# Shield_Play.net
KiCad netlist of a schematic drawn in EAGLE
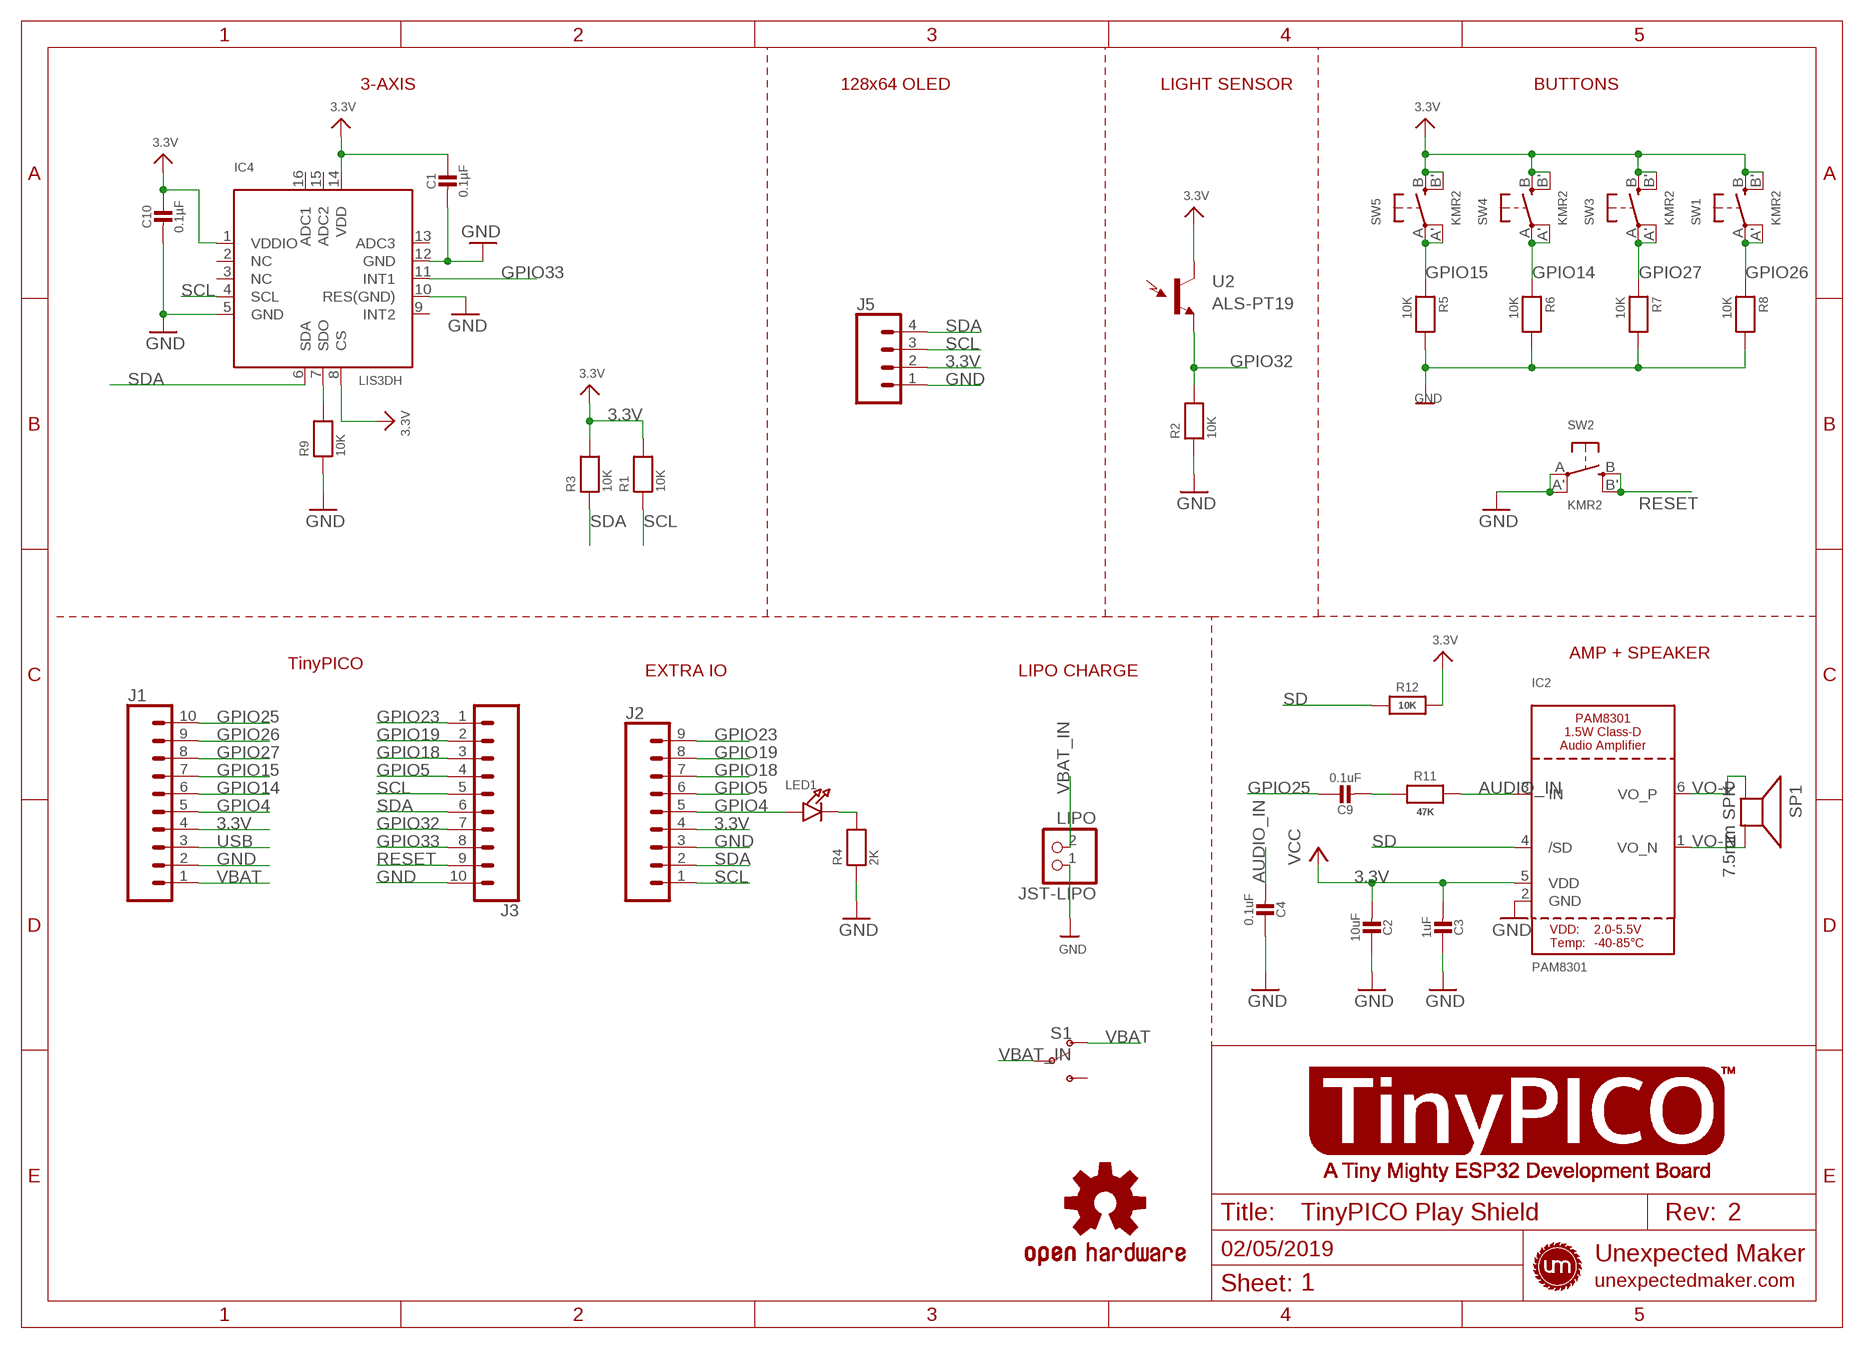
[diagram p0: schematic, sheet 1]

(export (version "E")
  (design (tool "Eeschema 10.0.6"))
  (components
    (comp (ref "C1")
      (value "0.1µF")
      (footprint "eagle-import:_0603MP")
      (libsource (lib "eagle-import") (part "CAP_CERAMIC_0603MP"))
    )
    (comp (ref "C2")
      (value "10uF")
      (footprint "eagle-import:_0603MP")
      (libsource (lib "eagle-import") (part "CAP_CERAMIC_0603MP"))
    )
    (comp (ref "C3")
      (value "1uF")
      (footprint "eagle-import:_0603MP")
      (libsource (lib "eagle-import") (part "CAP_CERAMIC_0603MP"))
    )
    (comp (ref "C4")
      (value "0.1uF")
      (footprint "eagle-import:_0603MP")
      (libsource (lib "eagle-import") (part "CAP_CERAMIC_0603MP"))
    )
    (comp (ref "C9")
      (value "0.1uF")
      (footprint "eagle-import:_0603MP")
      (libsource (lib "eagle-import") (part "CAP_CERAMIC_0603MP"))
    )
    (comp (ref "C10")
      (value "0.1µF")
      (footprint "eagle-import:_0603MP")
      (libsource (lib "eagle-import") (part "CAP_CERAMIC_0603MP"))
    )
    (comp (ref "IC2")
      (value "PAM8301")
      (footprint "eagle-import:SOT23-6")
      (libsource (lib "eagle-import") (part "PAM8301"))
    )
    (comp (ref "IC4")
      (value "LIS3DH")
      (footprint "eagle-import:LGA16_3X3MM")
      (libsource (lib "eagle-import") (part "ACCEL_LIS3DHTR"))
    )
    (comp (ref "J1")
      (value "TINYPICO_HEADER_10NO_SILK_PTH_FEMALE")
      (footprint "eagle-import:1X10_NO_SILK")
      (libsource (lib "eagle-import") (part "TINYPICO_HEADER_10NO_SILK_PTH_FEMALE"))
    )
    (comp (ref "J2")
      (value "CONN_09NO_SILK")
      (footprint "eagle-import:1X09_NO_SILK")
      (libsource (lib "eagle-import") (part "CONN_09NO_SILK"))
    )
    (comp (ref "J3")
      (value "TINYPICO_HEADER_10NO_SILK_PTH_FEMALE")
      (footprint "eagle-import:1X10_NO_SILK")
      (libsource (lib "eagle-import") (part "TINYPICO_HEADER_10NO_SILK_PTH_FEMALE"))
    )
    (comp (ref "J5")
      (value "CONN_041X04_NO_SILK")
      (footprint "eagle-import:1X04_NO_SILK")
      (libsource (lib "eagle-import") (part "CONN_041X04_NO_SILK"))
    )
    (comp (ref "JST-LIPO")
      (value "LIPO")
      (footprint "eagle-import:JSTPH2")
      (libsource (lib "eagle-import") (part "JST_2PIN"))
    )
    (comp (ref "LED1")
      (value "LED0603_NOOUTLINE")
      (footprint "eagle-import:CHIPLED_0603_NOOUTLINE")
      (libsource (lib "eagle-import") (part "LED0603_NOOUTLINE"))
    )
    (comp (ref "LOGO1")
      (value "OSHW-LOGOS")
      (footprint "eagle-import:OSHW-LOGO-S")
      (libsource (lib "eagle-import") (part "OSHW-LOGOS"))
    )
    (comp (ref "R1")
      (value "10K")
      (footprint "eagle-import:_0603MP")
      (libsource (lib "eagle-import") (part "RESISTOR_0603MP"))
    )
    (comp (ref "R2")
      (value "10K")
      (footprint "eagle-import:_0603MP")
      (libsource (lib "eagle-import") (part "RESISTOR_0603MP"))
    )
    (comp (ref "R3")
      (value "10K")
      (footprint "eagle-import:_0603MP")
      (libsource (lib "eagle-import") (part "RESISTOR_0603MP"))
    )
    (comp (ref "R4")
      (value "2K")
      (footprint "eagle-import:_0603MP")
      (libsource (lib "eagle-import") (part "RESISTOR_0603MP"))
    )
    (comp (ref "R5")
      (value "10K")
      (footprint "eagle-import:_0603MP")
      (libsource (lib "eagle-import") (part "RESISTOR_0603MP"))
    )
    (comp (ref "R6")
      (value "10K")
      (footprint "eagle-import:_0603MP")
      (libsource (lib "eagle-import") (part "RESISTOR_0603MP"))
    )
    (comp (ref "R7")
      (value "10K")
      (footprint "eagle-import:_0603MP")
      (libsource (lib "eagle-import") (part "RESISTOR_0603MP"))
    )
    (comp (ref "R8")
      (value "10K")
      (footprint "eagle-import:_0603MP")
      (libsource (lib "eagle-import") (part "RESISTOR_0603MP"))
    )
    (comp (ref "R9")
      (value "10K")
      (footprint "eagle-import:_0603MP")
      (libsource (lib "eagle-import") (part "RESISTOR_0603MP"))
    )
    (comp (ref "R11")
      (value "47K")
      (footprint "eagle-import:_0603MP")
      (libsource (lib "eagle-import") (part "RESISTOR_0603MP"))
    )
    (comp (ref "R12")
      (value "10K")
      (footprint "eagle-import:_0603MP")
      (libsource (lib "eagle-import") (part "RESISTOR_0603MP"))
    )
    (comp (ref "S1")
      (value "SPARKFUN-SWITCHES_SWITCH-SPDT-SMD-RIGHT-ANGLE")
      (footprint "eagle-import:SPARKFUN-SWITCHES_SWITCH_SPST_SMD_A")
      (libsource (lib "eagle-import") (part "SPARKFUN-SWITCHES_SWITCH-SPDT-SMD-RIGHT-ANGLE"))
    )
    (comp (ref "SP1")
      (value "7.5mm SPK")
      (footprint "eagle-import:BUZZER_SMT_7.5MM")
      (libsource (lib "eagle-import") (part "SPEAKER_7.5MM"))
    )
    (comp (ref "SW1")
      (value "KMR2")
      (footprint "eagle-import:BTN_KMR2_4.6X2.8")
      (libsource (lib "eagle-import") (part "SWITCH_TACT_SMT4.6X2.8"))
    )
    (comp (ref "SW2")
      (value "KMR2")
      (footprint "eagle-import:BTN_KMR2_4.6X2.8")
      (libsource (lib "eagle-import") (part "SWITCH_TACT_SMT4.6X2.8"))
    )
    (comp (ref "SW3")
      (value "KMR2")
      (footprint "eagle-import:BTN_KMR2_4.6X2.8")
      (libsource (lib "eagle-import") (part "SWITCH_TACT_SMT4.6X2.8"))
    )
    (comp (ref "SW4")
      (value "KMR2")
      (footprint "eagle-import:BTN_KMR2_4.6X2.8")
      (libsource (lib "eagle-import") (part "SWITCH_TACT_SMT4.6X2.8"))
    )
    (comp (ref "SW5")
      (value "KMR2")
      (footprint "eagle-import:BTN_KMR2_4.6X2.8")
      (libsource (lib "eagle-import") (part "SWITCH_TACT_SMT4.6X2.8"))
    )
    (comp (ref "U2")
      (value "ALS-PT19")
      (footprint "eagle-import:ALS-PT19")
      (libsource (lib "eagle-import") (part "LIGHT_SENSORALS"))
    )
  )
  (nets
    (net (code "1") (name "/AUDIO_IN") (class "Default")
      (node (ref "C4") (pin "2") (pinfunction "2_2") (pintype "passive"))
      (node (ref "IC2") (pin "3") (pinfunction "IN_3") (pintype "input"))
      (node (ref "R11") (pin "2") (pinfunction "2_2") (pintype "passive"))
    )
    (net (code "2") (name "/GPIO4") (class "Default")
      (node (ref "J1") (pin "5") (pinfunction "5_5") (pintype "passive"))
      (node (ref "J2") (pin "5") (pinfunction "5_5") (pintype "passive"))
      (node (ref "LED1") (pin "A") (pinfunction "A_A") (pintype "passive"))
    )
    (net (code "3") (name "/GPIO5") (class "Default")
      (node (ref "J2") (pin "6") (pinfunction "6_6") (pintype "passive"))
      (node (ref "J3") (pin "4") (pinfunction "4_4") (pintype "passive"))
    )
    (net (code "4") (name "/GPIO14") (class "Default")
      (node (ref "J1") (pin "6") (pinfunction "6_6") (pintype "passive"))
      (node (ref "R6") (pin "1") (pinfunction "1_1") (pintype "passive"))
      (node (ref "SW4") (pin "A") (pinfunction "P_A") (pintype "passive"))
      (node (ref "SW4") (pin "A'") (pinfunction "P1_A'") (pintype "passive"))
    )
    (net (code "5") (name "/GPIO15") (class "Default")
      (node (ref "J1") (pin "7") (pinfunction "7_7") (pintype "passive"))
      (node (ref "R5") (pin "1") (pinfunction "1_1") (pintype "passive"))
      (node (ref "SW5") (pin "A") (pinfunction "P_A") (pintype "passive"))
      (node (ref "SW5") (pin "A'") (pinfunction "P1_A'") (pintype "passive"))
    )
    (net (code "6") (name "/GPIO18") (class "Default")
      (node (ref "J2") (pin "7") (pinfunction "7_7") (pintype "passive"))
      (node (ref "J3") (pin "3") (pinfunction "3_3") (pintype "passive"))
    )
    (net (code "7") (name "/GPIO19") (class "Default")
      (node (ref "J2") (pin "8") (pinfunction "8_8") (pintype "passive"))
      (node (ref "J3") (pin "2") (pinfunction "2_2") (pintype "passive"))
    )
    (net (code "8") (name "/GPIO23") (class "Default")
      (node (ref "J2") (pin "9") (pinfunction "9_9") (pintype "passive"))
      (node (ref "J3") (pin "1") (pinfunction "1_1") (pintype "passive"))
    )
    (net (code "9") (name "/GPIO25") (class "Default")
      (node (ref "C9") (pin "1") (pinfunction "1_1") (pintype "passive"))
      (node (ref "J1") (pin "10") (pinfunction "10_10") (pintype "passive"))
    )
    (net (code "10") (name "/GPIO26") (class "Default")
      (node (ref "J1") (pin "9") (pinfunction "9_9") (pintype "passive"))
      (node (ref "R8") (pin "1") (pinfunction "1_1") (pintype "passive"))
      (node (ref "SW1") (pin "A") (pinfunction "P_A") (pintype "passive"))
      (node (ref "SW1") (pin "A'") (pinfunction "P1_A'") (pintype "passive"))
    )
    (net (code "11") (name "/GPIO27") (class "Default")
      (node (ref "J1") (pin "8") (pinfunction "8_8") (pintype "passive"))
      (node (ref "R7") (pin "1") (pinfunction "1_1") (pintype "passive"))
      (node (ref "SW3") (pin "A") (pinfunction "P_A") (pintype "passive"))
      (node (ref "SW3") (pin "A'") (pinfunction "P1_A'") (pintype "passive"))
    )
    (net (code "12") (name "/GPIO32") (class "Default")
      (node (ref "J3") (pin "7") (pinfunction "7_7") (pintype "passive"))
      (node (ref "R2") (pin "2") (pinfunction "2_2") (pintype "passive"))
      (node (ref "U2") (pin "E") (pinfunction "E1_E") (pintype "passive"))
    )
    (net (code "13") (name "/GPIO33") (class "Default")
      (node (ref "IC4") (pin "11") (pinfunction "INT1_11") (pintype "output"))
      (node (ref "J3") (pin "8") (pinfunction "8_8") (pintype "passive"))
    )
    (net (code "14") (name "/RESET") (class "Default")
      (node (ref "J3") (pin "9") (pinfunction "9_9") (pintype "passive"))
      (node (ref "SW2") (pin "B") (pinfunction "S_B") (pintype "passive"))
      (node (ref "SW2") (pin "B'") (pinfunction "S1_B'") (pintype "passive"))
    )
    (net (code "15") (name "/SCL") (class "Default")
      (node (ref "IC4") (pin "4") (pinfunction "SCL_4") (pintype "bidirectional"))
      (node (ref "J2") (pin "1") (pinfunction "1_1") (pintype "passive"))
      (node (ref "J3") (pin "5") (pinfunction "5_5") (pintype "passive"))
      (node (ref "J5") (pin "3") (pinfunction "3_3") (pintype "passive"))
      (node (ref "R1") (pin "1") (pinfunction "1_1") (pintype "passive"))
    )
    (net (code "16") (name "/SD") (class "Default")
      (node (ref "IC2") (pin "4") (pinfunction "/SD_4") (pintype "input"))
      (node (ref "R12") (pin "1") (pinfunction "1_1") (pintype "passive"))
    )
    (net (code "17") (name "/SDA") (class "Default")
      (node (ref "IC4") (pin "6") (pinfunction "SDA_6") (pintype "bidirectional"))
      (node (ref "J2") (pin "2") (pinfunction "2_2") (pintype "passive"))
      (node (ref "J3") (pin "6") (pinfunction "6_6") (pintype "passive"))
      (node (ref "J5") (pin "4") (pinfunction "4_4") (pintype "passive"))
      (node (ref "R3") (pin "1") (pinfunction "1_1") (pintype "passive"))
    )
    (net (code "18") (name "/USB") (class "Default")
      (node (ref "J1") (pin "3") (pinfunction "3_3") (pintype "passive"))
    )
    (net (code "19") (name "/VBAT") (class "Default")
      (node (ref "J1") (pin "1") (pinfunction "1_1") (pintype "passive"))
      (node (ref "S1") (pin "1") (pinfunction "O_1") (pintype "passive"))
    )
    (net (code "20") (name "/VBAT_IN") (class "Default")
      (node (ref "JST-LIPO") (pin "2") (pinfunction "2_2") (pintype "passive"))
      (node (ref "S1") (pin "2") (pinfunction "P_2") (pintype "passive"))
    )
    (net (code "21") (name "/VO-N") (class "Default")
      (node (ref "IC2") (pin "1") (pinfunction "VO_N_1") (pintype "output"))
      (node (ref "SP1") (pin "-") (pinfunction "-_-") (pintype "passive"))
    )
    (net (code "22") (name "/VO-P") (class "Default")
      (node (ref "IC2") (pin "6") (pinfunction "VO_P_6") (pintype "output"))
      (node (ref "SP1") (pin "+") (pinfunction "+_+") (pintype "passive"))
    )
    (net (code "23") (name "3.3V") (class "Default")
      (node (ref "C1") (pin "1") (pinfunction "1_1") (pintype "passive"))
      (node (ref "C10") (pin "1") (pinfunction "1_1") (pintype "passive"))
      (node (ref "C2") (pin "2") (pinfunction "2_2") (pintype "passive"))
      (node (ref "C3") (pin "2") (pinfunction "2_2") (pintype "passive"))
      (node (ref "IC2") (pin "5") (pinfunction "VDD_5") (pintype "power_in"))
      (node (ref "IC4") (pin "1") (pinfunction "VDDIO_1") (pintype "power_in"))
      (node (ref "IC4") (pin "14") (pinfunction "VDD_14") (pintype "power_in"))
      (node (ref "IC4") (pin "8") (pinfunction "CS_8") (pintype "input"))
      (node (ref "J1") (pin "4") (pinfunction "4_4") (pintype "passive"))
      (node (ref "J2") (pin "4") (pinfunction "4_4") (pintype "passive"))
      (node (ref "J5") (pin "2") (pinfunction "2_2") (pintype "passive"))
      (node (ref "R1") (pin "2") (pinfunction "2_2") (pintype "passive"))
      (node (ref "R12") (pin "2") (pinfunction "2_2") (pintype "passive"))
      (node (ref "R3") (pin "2") (pinfunction "2_2") (pintype "passive"))
      (node (ref "SW1") (pin "B") (pinfunction "S_B") (pintype "passive"))
      (node (ref "SW1") (pin "B'") (pinfunction "S1_B'") (pintype "passive"))
      (node (ref "SW3") (pin "B") (pinfunction "S_B") (pintype "passive"))
      (node (ref "SW3") (pin "B'") (pinfunction "S1_B'") (pintype "passive"))
      (node (ref "SW4") (pin "B") (pinfunction "S_B") (pintype "passive"))
      (node (ref "SW4") (pin "B'") (pinfunction "S1_B'") (pintype "passive"))
      (node (ref "SW5") (pin "B") (pinfunction "S_B") (pintype "passive"))
      (node (ref "SW5") (pin "B'") (pinfunction "S1_B'") (pintype "passive"))
      (node (ref "U2") (pin "C") (pinfunction "C1_C") (pintype "passive"))
    )
    (net (code "24") (name "GND") (class "Default")
      (node (ref "C1") (pin "2") (pinfunction "2_2") (pintype "passive"))
      (node (ref "C10") (pin "2") (pinfunction "2_2") (pintype "passive"))
      (node (ref "C2") (pin "1") (pinfunction "1_1") (pintype "passive"))
      (node (ref "C3") (pin "1") (pinfunction "1_1") (pintype "passive"))
      (node (ref "C4") (pin "1") (pinfunction "1_1") (pintype "passive"))
      (node (ref "IC2") (pin "2") (pinfunction "GND_2") (pintype "power_in"))
      (node (ref "IC4") (pin "10") (pinfunction "RES(GND)_10") (pintype "bidirectional"))
      (node (ref "IC4") (pin "12") (pinfunction "GND_12") (pintype "power_in"))
      (node (ref "IC4") (pin "5") (pinfunction "GND_5") (pintype "power_in"))
      (node (ref "J1") (pin "2") (pinfunction "2_2") (pintype "passive"))
      (node (ref "J2") (pin "3") (pinfunction "3_3") (pintype "passive"))
      (node (ref "J3") (pin "10") (pinfunction "10_10") (pintype "passive"))
      (node (ref "J5") (pin "1") (pinfunction "1_1") (pintype "passive"))
      (node (ref "JST-LIPO") (pin "1") (pinfunction "1_1") (pintype "passive"))
      (node (ref "R2") (pin "1") (pinfunction "1_1") (pintype "passive"))
      (node (ref "R4") (pin "1") (pinfunction "1_1") (pintype "passive"))
      (node (ref "R5") (pin "2") (pinfunction "2_2") (pintype "passive"))
      (node (ref "R6") (pin "2") (pinfunction "2_2") (pintype "passive"))
      (node (ref "R7") (pin "2") (pinfunction "2_2") (pintype "passive"))
      (node (ref "R8") (pin "2") (pinfunction "2_2") (pintype "passive"))
      (node (ref "R9") (pin "1") (pinfunction "1_1") (pintype "passive"))
      (node (ref "SW2") (pin "A") (pinfunction "P_A") (pintype "passive"))
      (node (ref "SW2") (pin "A'") (pinfunction "P1_A'") (pintype "passive"))
    )
    (net (code "25") (name "Net-(C9-Pad2)") (class "Default")
      (node (ref "C9") (pin "2") (pinfunction "2_2") (pintype "passive"))
      (node (ref "R11") (pin "1") (pinfunction "1_1") (pintype "passive"))
    )
    (net (code "26") (name "Net-(IC4-SDO)") (class "Default")
      (node (ref "IC4") (pin "7") (pinfunction "SDO_7") (pintype "bidirectional"))
      (node (ref "R9") (pin "2") (pinfunction "2_2") (pintype "passive"))
    )
    (net (code "27") (name "Net-(LED1-PadC)") (class "Default")
      (node (ref "LED1") (pin "C") (pinfunction "C_C") (pintype "passive"))
      (node (ref "R4") (pin "2") (pinfunction "2_2") (pintype "passive"))
    )
    (net (code "28") (name "unconnected-(IC4-ADC1-Pad16)") (class "Default")
      (node (ref "IC4") (pin "16") (pinfunction "ADC1_16") (pintype "input"))
    )
    (net (code "29") (name "unconnected-(IC4-ADC2-Pad15)") (class "Default")
      (node (ref "IC4") (pin "15") (pinfunction "ADC2_15") (pintype "input"))
    )
    (net (code "30") (name "unconnected-(IC4-ADC3-Pad13)") (class "Default")
      (node (ref "IC4") (pin "13") (pinfunction "ADC3_13") (pintype "input"))
    )
    (net (code "31") (name "unconnected-(IC4-INT2-Pad9)") (class "Default")
      (node (ref "IC4") (pin "9") (pinfunction "INT2_9") (pintype "output"))
    )
    (net (code "32") (name "unconnected-(IC4-NC-Pad2)") (class "Default")
      (node (ref "IC4") (pin "2") (pinfunction "NC_2") (pintype "no_connect"))
    )
    (net (code "33") (name "unconnected-(IC4-NC-Pad3)") (class "Default")
      (node (ref "IC4") (pin "3") (pinfunction "NC_3") (pintype "no_connect"))
    )
    (net (code "34") (name "unconnected-(S1-S-Pad3)") (class "Default")
      (node (ref "S1") (pin "3") (pinfunction "S_3") (pintype "passive"))
    )
  )
)
